# uart_rs232_adapter.net
KiCad netlist of a schematic drawn in EAGLE
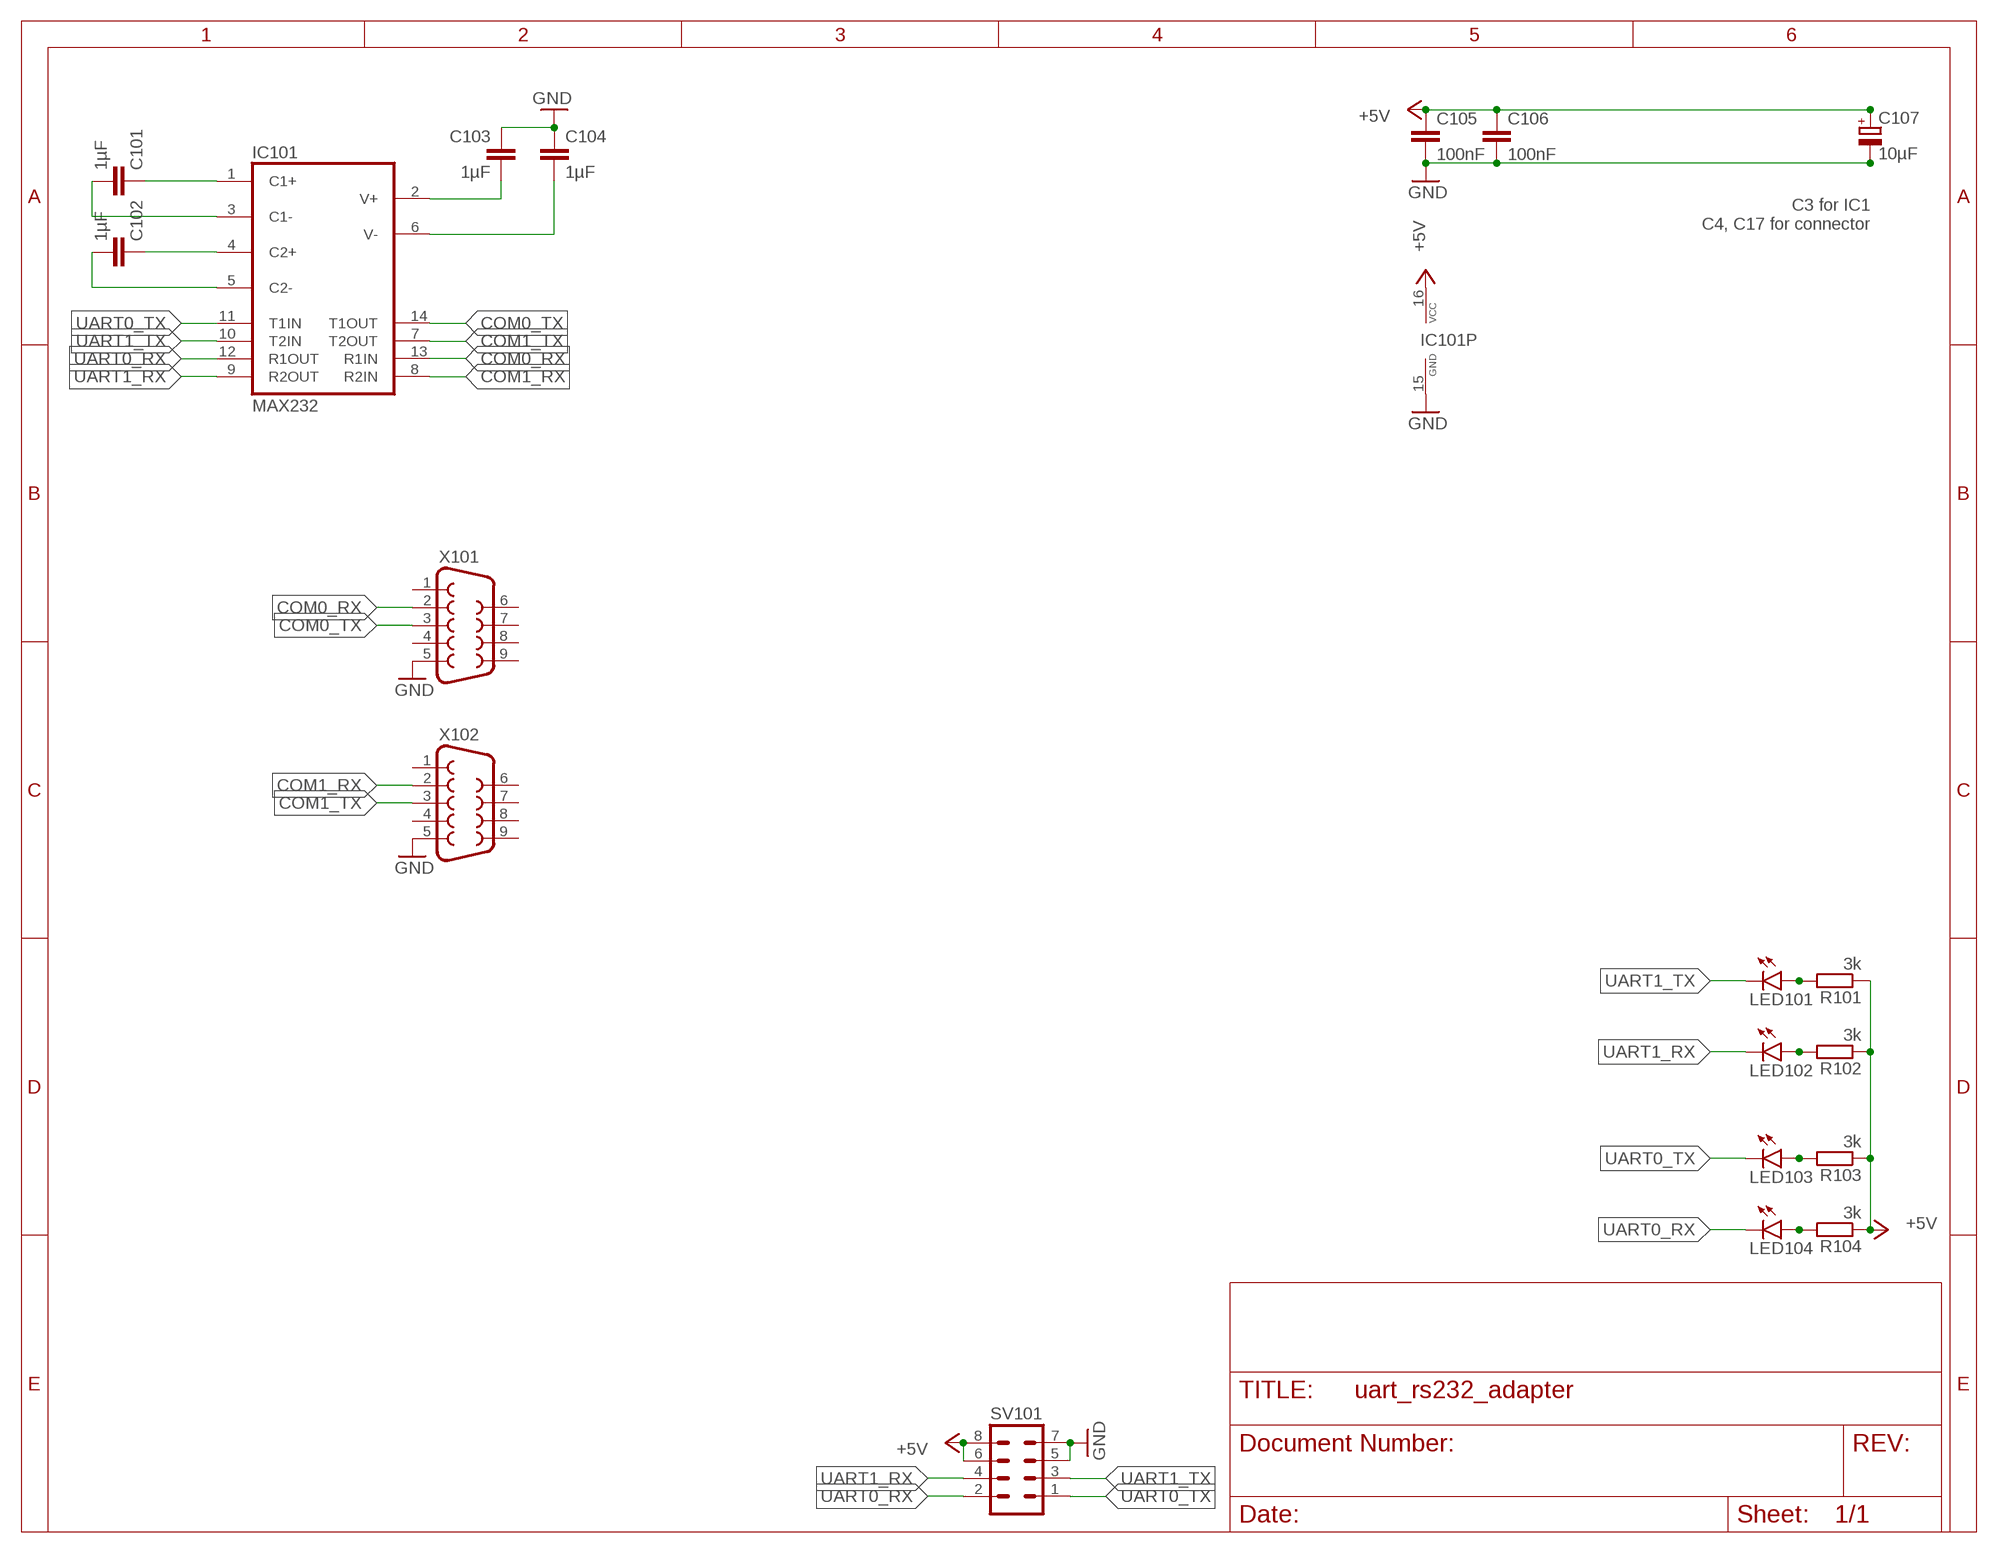
[diagram p0: schematic, sheet 1]

(export (version "E")
  (design (tool "Eeschema 10.0.6"))
  (components
    (comp (ref "C101")
      (value "1µF")
      (footprint "eagle-import:C0805")
      (libsource (lib "eagle-import") (part "C-EUC0805"))
    )
    (comp (ref "C102")
      (value "1µF")
      (footprint "eagle-import:C0805")
      (libsource (lib "eagle-import") (part "C-EUC0805"))
    )
    (comp (ref "C103")
      (value "1µF")
      (footprint "eagle-import:C0805")
      (libsource (lib "eagle-import") (part "C-EUC0805"))
    )
    (comp (ref "C104")
      (value "1µF")
      (footprint "eagle-import:C0805")
      (libsource (lib "eagle-import") (part "C-EUC0805"))
    )
    (comp (ref "C105")
      (value "100nF")
      (footprint "eagle-import:C0805")
      (libsource (lib "eagle-import") (part "C-EUC0805"))
    )
    (comp (ref "C106")
      (value "100nF")
      (footprint "eagle-import:C0805")
      (libsource (lib "eagle-import") (part "C-EUC0805"))
    )
    (comp (ref "C107")
      (value "10µF")
      (footprint "eagle-import:SMC_B")
      (libsource (lib "eagle-import") (part "CPOL-EUSMCB"))
    )
    (comp (ref "IC101")
      (value "MAX232")
      (footprint "eagle-import:DIL16")
      (fields
        (field (name "MF") "MAXIM")
        (field (name "MPN") "MAX232ACPE+")
        (field (name "MOUSER") "595-MAX232ECN")
      )
      (libsource (lib "eagle-import") (part "MAX232"))
    )
    (comp (ref "LED101")
      (value "LEDCHIPLED_1206")
      (footprint "eagle-import:CHIPLED_1206")
      (libsource (lib "eagle-import") (part "LEDCHIPLED_1206"))
    )
    (comp (ref "LED102")
      (value "LEDCHIPLED_1206")
      (footprint "eagle-import:CHIPLED_1206")
      (libsource (lib "eagle-import") (part "LEDCHIPLED_1206"))
    )
    (comp (ref "LED103")
      (value "LEDCHIPLED_1206")
      (footprint "eagle-import:CHIPLED_1206")
      (libsource (lib "eagle-import") (part "LEDCHIPLED_1206"))
    )
    (comp (ref "LED104")
      (value "LEDCHIPLED_1206")
      (footprint "eagle-import:CHIPLED_1206")
      (libsource (lib "eagle-import") (part "LEDCHIPLED_1206"))
    )
    (comp (ref "R101")
      (value "3k")
      (footprint "eagle-import:R2012")
      (libsource (lib "eagle-import") (part "R-EU_R2012"))
    )
    (comp (ref "R102")
      (value "3k")
      (footprint "eagle-import:R2012")
      (libsource (lib "eagle-import") (part "R-EU_R2012"))
    )
    (comp (ref "R103")
      (value "3k")
      (footprint "eagle-import:R2012")
      (libsource (lib "eagle-import") (part "R-EU_R2012"))
    )
    (comp (ref "R104")
      (value "3k")
      (footprint "eagle-import:R2012")
      (libsource (lib "eagle-import") (part "R-EU_R2012"))
    )
    (comp (ref "SV101")
      (value "MA04-2")
      (footprint "eagle-import:MA04-2")
      (libsource (lib "eagle-import") (part "MA04-2"))
    )
    (comp (ref "X101")
      (value "F09HP")
      (footprint "eagle-import:F09HP")
      (libsource (lib "eagle-import") (part "F09HP"))
    )
    (comp (ref "X102")
      (value "F09HP")
      (footprint "eagle-import:F09HP")
      (libsource (lib "eagle-import") (part "F09HP"))
    )
  )
  (nets
    (net (code "1") (name "+5V") (class "Default")
      (node (ref "C105") (pin "1") (pinfunction "1_1") (pintype "passive"))
      (node (ref "C106") (pin "1") (pinfunction "1_1") (pintype "passive"))
      (node (ref "C107") (pin "+") (pinfunction "+_+") (pintype "passive"))
      (node (ref "IC101") (pin "16") (pinfunction "VCC_16") (pintype "power_in"))
      (node (ref "R101") (pin "1") (pinfunction "1_1") (pintype "passive"))
      (node (ref "R102") (pin "1") (pinfunction "1_1") (pintype "passive"))
      (node (ref "R103") (pin "1") (pinfunction "1_1") (pintype "passive"))
      (node (ref "R104") (pin "1") (pinfunction "1_1") (pintype "passive"))
      (node (ref "SV101") (pin "6") (pinfunction "6_6") (pintype "passive"))
      (node (ref "SV101") (pin "8") (pinfunction "8_8") (pintype "passive"))
    )
    (net (code "2") (name "COM0_RX") (class "Default")
      (node (ref "IC101") (pin "13") (pinfunction "R1IN_13") (pintype "input"))
      (node (ref "X101") (pin "2") (pinfunction "2_2") (pintype "passive"))
    )
    (net (code "3") (name "COM0_TX") (class "Default")
      (node (ref "IC101") (pin "14") (pinfunction "T1OUT_14") (pintype "output"))
      (node (ref "X101") (pin "3") (pinfunction "3_3") (pintype "passive"))
    )
    (net (code "4") (name "COM1_RX") (class "Default")
      (node (ref "IC101") (pin "8") (pinfunction "R2IN_8") (pintype "input"))
      (node (ref "X102") (pin "2") (pinfunction "2_2") (pintype "passive"))
    )
    (net (code "5") (name "COM1_TX") (class "Default")
      (node (ref "IC101") (pin "7") (pinfunction "T2OUT_7") (pintype "output"))
      (node (ref "X102") (pin "3") (pinfunction "3_3") (pintype "passive"))
    )
    (net (code "6") (name "GND") (class "Default")
      (node (ref "C103") (pin "1") (pinfunction "1_1") (pintype "passive"))
      (node (ref "C104") (pin "1") (pinfunction "1_1") (pintype "passive"))
      (node (ref "C105") (pin "2") (pinfunction "2_2") (pintype "passive"))
      (node (ref "C106") (pin "2") (pinfunction "2_2") (pintype "passive"))
      (node (ref "C107") (pin "-") (pinfunction "-_-") (pintype "passive"))
      (node (ref "IC101") (pin "15") (pinfunction "GND_15") (pintype "power_in"))
      (node (ref "SV101") (pin "5") (pinfunction "5_5") (pintype "passive"))
      (node (ref "SV101") (pin "7") (pinfunction "7_7") (pintype "passive"))
      (node (ref "X101") (pin "5") (pinfunction "5_5") (pintype "passive"))
      (node (ref "X102") (pin "5") (pinfunction "5_5") (pintype "passive"))
    )
    (net (code "7") (name "Net-(IC101A-C1+)") (class "Default")
      (node (ref "C101") (pin "1") (pinfunction "1_1") (pintype "passive"))
      (node (ref "IC101") (pin "1") (pinfunction "C1+_1") (pintype "bidirectional"))
    )
    (net (code "8") (name "Net-(IC101A-C1-)") (class "Default")
      (node (ref "C101") (pin "2") (pinfunction "2_2") (pintype "passive"))
      (node (ref "IC101") (pin "3") (pinfunction "C1-_3") (pintype "bidirectional"))
    )
    (net (code "9") (name "Net-(IC101A-C2+)") (class "Default")
      (node (ref "C102") (pin "1") (pinfunction "1_1") (pintype "passive"))
      (node (ref "IC101") (pin "4") (pinfunction "C2+_4") (pintype "bidirectional"))
    )
    (net (code "10") (name "Net-(IC101A-C2-)") (class "Default")
      (node (ref "C102") (pin "2") (pinfunction "2_2") (pintype "passive"))
      (node (ref "IC101") (pin "5") (pinfunction "C2-_5") (pintype "bidirectional"))
    )
    (net (code "11") (name "Net-(IC101A-V+)") (class "Default")
      (node (ref "C103") (pin "2") (pinfunction "2_2") (pintype "passive"))
      (node (ref "IC101") (pin "2") (pinfunction "V+_2") (pintype "bidirectional"))
    )
    (net (code "12") (name "Net-(IC101A-V-)") (class "Default")
      (node (ref "C104") (pin "2") (pinfunction "2_2") (pintype "passive"))
      (node (ref "IC101") (pin "6") (pinfunction "V-_6") (pintype "bidirectional"))
    )
    (net (code "13") (name "Net-(LED101-PadA)") (class "Default")
      (node (ref "LED101") (pin "A") (pinfunction "A_A") (pintype "passive"))
      (node (ref "R101") (pin "2") (pinfunction "2_2") (pintype "passive"))
    )
    (net (code "14") (name "Net-(LED102-PadA)") (class "Default")
      (node (ref "LED102") (pin "A") (pinfunction "A_A") (pintype "passive"))
      (node (ref "R102") (pin "2") (pinfunction "2_2") (pintype "passive"))
    )
    (net (code "15") (name "Net-(LED103-PadA)") (class "Default")
      (node (ref "LED103") (pin "A") (pinfunction "A_A") (pintype "passive"))
      (node (ref "R103") (pin "2") (pinfunction "2_2") (pintype "passive"))
    )
    (net (code "16") (name "Net-(LED104-PadA)") (class "Default")
      (node (ref "LED104") (pin "A") (pinfunction "A_A") (pintype "passive"))
      (node (ref "R104") (pin "2") (pinfunction "2_2") (pintype "passive"))
    )
    (net (code "17") (name "UART0_RX") (class "Default")
      (node (ref "IC101") (pin "12") (pinfunction "R1OUT_12") (pintype "output"))
      (node (ref "LED104") (pin "C") (pinfunction "C_C") (pintype "passive"))
      (node (ref "SV101") (pin "2") (pinfunction "2_2") (pintype "passive"))
    )
    (net (code "18") (name "UART0_TX") (class "Default")
      (node (ref "IC101") (pin "11") (pinfunction "T1IN_11") (pintype "input"))
      (node (ref "LED103") (pin "C") (pinfunction "C_C") (pintype "passive"))
      (node (ref "SV101") (pin "1") (pinfunction "1_1") (pintype "passive"))
    )
    (net (code "19") (name "UART1_RX") (class "Default")
      (node (ref "IC101") (pin "9") (pinfunction "R2OUT_9") (pintype "output"))
      (node (ref "LED102") (pin "C") (pinfunction "C_C") (pintype "passive"))
      (node (ref "SV101") (pin "4") (pinfunction "4_4") (pintype "passive"))
    )
    (net (code "20") (name "UART1_TX") (class "Default")
      (node (ref "IC101") (pin "10") (pinfunction "T2IN_10") (pintype "input"))
      (node (ref "LED101") (pin "C") (pinfunction "C_C") (pintype "passive"))
      (node (ref "SV101") (pin "3") (pinfunction "3_3") (pintype "passive"))
    )
    (net (code "21") (name "unconnected-(X101-Pad1)") (class "Default")
      (node (ref "X101") (pin "1") (pinfunction "1_1") (pintype "passive"))
    )
    (net (code "22") (name "unconnected-(X101-Pad4)") (class "Default")
      (node (ref "X101") (pin "4") (pinfunction "4_4") (pintype "passive"))
    )
    (net (code "23") (name "unconnected-(X101-Pad6)") (class "Default")
      (node (ref "X101") (pin "6") (pinfunction "6_6") (pintype "passive"))
    )
    (net (code "24") (name "unconnected-(X101-Pad7)") (class "Default")
      (node (ref "X101") (pin "7") (pinfunction "7_7") (pintype "passive"))
    )
    (net (code "25") (name "unconnected-(X101-Pad8)") (class "Default")
      (node (ref "X101") (pin "8") (pinfunction "8_8") (pintype "passive"))
    )
    (net (code "26") (name "unconnected-(X101-Pad9)") (class "Default")
      (node (ref "X101") (pin "9") (pinfunction "9_9") (pintype "passive"))
    )
    (net (code "27") (name "unconnected-(X102-Pad1)") (class "Default")
      (node (ref "X102") (pin "1") (pinfunction "1_1") (pintype "passive"))
    )
    (net (code "28") (name "unconnected-(X102-Pad4)") (class "Default")
      (node (ref "X102") (pin "4") (pinfunction "4_4") (pintype "passive"))
    )
    (net (code "29") (name "unconnected-(X102-Pad6)") (class "Default")
      (node (ref "X102") (pin "6") (pinfunction "6_6") (pintype "passive"))
    )
    (net (code "30") (name "unconnected-(X102-Pad7)") (class "Default")
      (node (ref "X102") (pin "7") (pinfunction "7_7") (pintype "passive"))
    )
    (net (code "31") (name "unconnected-(X102-Pad8)") (class "Default")
      (node (ref "X102") (pin "8") (pinfunction "8_8") (pintype "passive"))
    )
    (net (code "32") (name "unconnected-(X102-Pad9)") (class "Default")
      (node (ref "X102") (pin "9") (pinfunction "9_9") (pintype "passive"))
    )
  )
)
